# SCH_Modules.net
KiCad netlist of a schematic drawn in Altium Designer
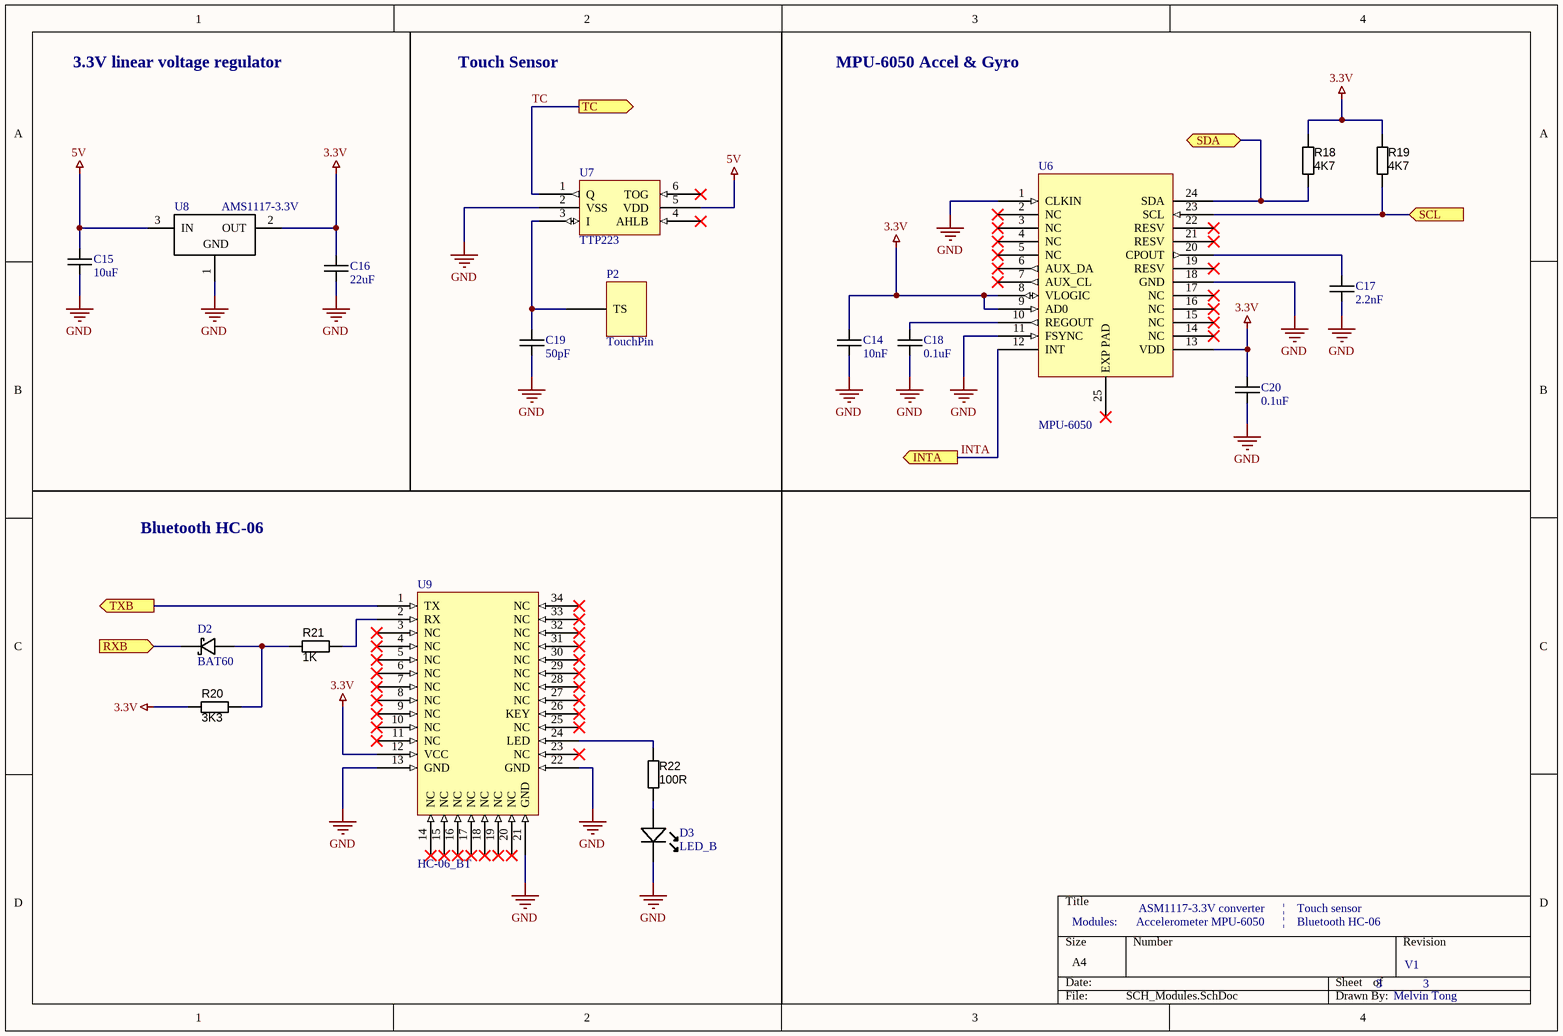
[diagram p0: SCH_Modules.SchDoc]

(export (version "E")
  (design (tool "Eeschema 10.0.6"))
  (components
    (comp (ref "C14")
      (value "10nF")
      (footprint "CAP_0805")
      (description "SMD 0805")
      (libsource (lib "Schlib_Sword") (part "CAP_10nF"))
    )
    (comp (ref "C15")
      (value "10uF")
      (footprint "CAP_1206")
      (description "SMD 0805/1206")
      (libsource (lib "Schlib_Sword") (part "CAP_10uF"))
    )
    (comp (ref "C16")
      (value "22uF")
      (footprint "CAP_1206")
      (description "SMD 1206")
      (libsource (lib "Schlib_Sword") (part "CAP_22uF"))
    )
    (comp (ref "C17")
      (value "2.2nF")
      (footprint "CAP_0805")
      (description "SMD 0805")
      (libsource (lib "Schlib_Sword") (part "CAP_2.2nF"))
    )
    (comp (ref "C18")
      (value "0.1uF")
      (footprint "CAP_0805")
      (description "SMD 0805")
      (libsource (lib "Schlib_Sword") (part "CAP_0.1uF"))
    )
    (comp (ref "C19")
      (value "50pF")
      (footprint "CAP_0805")
      (description "SMD 0805")
      (libsource (lib "Schlib_Sword") (part "CAP_50pF"))
    )
    (comp (ref "C20")
      (value "0.1uF")
      (footprint "CAP_0805")
      (description "SMD 0805")
      (libsource (lib "Schlib_Sword") (part "CAP_0.1uF"))
    )
    (comp (ref "D2")
      (value "BAT60")
      (footprint "SOD323")
      (description "Schottky Diode 3A, Vf~0.24V, Vr=10V")
      (libsource (lib "Schlib_Sword") (part "BAT60"))
    )
    (comp (ref "D3")
      (value "LED_B")
      (footprint "LED_0805")
      (description "SMD_0805 3V")
      (libsource (lib "Schlib_Sword") (part "LED_B"))
    )
    (comp (ref "P2")
      (value "TouchPin")
      (footprint "TouchPad")
      (libsource (lib "Schlib_Sword") (part "TouchPin"))
    )
    (comp (ref "R18")
      (value "4K7")
      (footprint "RESC3216X70N")
      (description "Resistor SMD, 1206")
      (libsource (lib "Schlib_Sword") (part "RES_4K7"))
    )
    (comp (ref "R19")
      (value "4K7")
      (footprint "RESC3216X70N")
      (description "Resistor SMD, 1206")
      (libsource (lib "Schlib_Sword") (part "RES_4K7"))
    )
    (comp (ref "R20")
      (value "3K3")
      (footprint "RESC3216X70N")
      (description "Resistor SMD, 1206")
      (libsource (lib "Schlib_Sword") (part "RES_3K3"))
    )
    (comp (ref "R21")
      (value "1K")
      (footprint "RESC3216X70N")
      (description "Resistor SMD, 1206")
      (libsource (lib "Schlib_Sword") (part "RES_1K"))
    )
    (comp (ref "R22")
      (value "100R")
      (footprint "RESC3216X70N")
      (description "Resistor SMD, 1206")
      (libsource (lib "Schlib_Sword") (part "RES_100R"))
    )
    (comp (ref "U6")
      (value "MPU-6050")
      (footprint "MPU-6050")
      (libsource (lib "Schlib_Sword") (part "MPU-6050"))
    )
    (comp (ref "U7")
      (value "TTP223")
      (footprint "TTP223-BA6")
      (libsource (lib "Schlib_Sword") (part "TTP223"))
    )
    (comp (ref "U8")
      (value "AMS1117-3.3V")
      (footprint "SOT223")
      (libsource (lib "Schlib_Sword") (part "AMS1117-3.3V"))
    )
    (comp (ref "U9")
      (value "HC-06_BT")
      (footprint "HC-06_BT")
      (libsource (lib "Schlib_Sword") (part "HC-06_BT"))
    )
  )
  (nets
    (net (code "1") (name "/INTA") (class "Default")
      (node (ref "U6") (pin "12") (pinfunction "INT_12") (pintype "open_collector"))
    )
    (net (code "2") (name "/RXB") (class "Default")
      (node (ref "D2") (pin "K") (pinfunction "K_K") (pintype "passive"))
    )
    (net (code "3") (name "/SCL") (class "Default")
      (node (ref "R19") (pin "2") (pinfunction "2_2") (pintype "passive"))
      (node (ref "U6") (pin "23") (pinfunction "SCL_23") (pintype "input"))
    )
    (net (code "4") (name "/SDA") (class "Default")
      (node (ref "R18") (pin "2") (pinfunction "2_2") (pintype "passive"))
      (node (ref "U6") (pin "24") (pinfunction "SDA_24") (pintype "open_collector"))
    )
    (net (code "5") (name "/TC") (class "Default")
      (node (ref "U7") (pin "1") (pinfunction "Q_1") (pintype "output"))
    )
    (net (code "6") (name "/TXB") (class "Default")
      (node (ref "U9") (pin "1") (pinfunction "TX_1") (pintype "input"))
    )
    (net (code "7") (name "3.3V") (class "Default")
      (node (ref "C14") (pin "2") (pintype "passive"))
      (node (ref "C16") (pin "1") (pintype "passive"))
      (node (ref "C20") (pin "2") (pintype "passive"))
      (node (ref "R18") (pin "1") (pinfunction "1_1") (pintype "passive"))
      (node (ref "R19") (pin "1") (pinfunction "1_1") (pintype "passive"))
      (node (ref "R20") (pin "1") (pinfunction "1_1") (pintype "passive"))
      (node (ref "U6") (pin "13") (pinfunction "VDD_13") (pintype "power_in"))
      (node (ref "U6") (pin "8") (pinfunction "VLOGIC_8") (pintype "bidirectional"))
      (node (ref "U6") (pin "9") (pinfunction "AD0_9") (pintype "input"))
      (node (ref "U8") (pin "2") (pinfunction "OUT_2") (pintype "power_in"))
      (node (ref "U9") (pin "12") (pinfunction "VCC_12") (pintype "input"))
    )
    (net (code "8") (name "5V") (class "Default")
      (node (ref "C15") (pin "1") (pintype "passive"))
      (node (ref "U7") (pin "5") (pinfunction "VDD_5") (pintype "power_in"))
      (node (ref "U8") (pin "3") (pinfunction "IN_3") (pintype "power_in"))
    )
    (net (code "9") (name "GND") (class "Default")
      (node (ref "C14") (pin "1") (pintype "passive"))
      (node (ref "C15") (pin "2") (pintype "passive"))
      (node (ref "C16") (pin "2") (pintype "passive"))
      (node (ref "C17") (pin "2") (pintype "passive"))
      (node (ref "C18") (pin "1") (pintype "passive"))
      (node (ref "C19") (pin "2") (pintype "passive"))
      (node (ref "C20") (pin "1") (pintype "passive"))
      (node (ref "D3") (pin "K") (pinfunction "K_K") (pintype "passive"))
      (node (ref "U6") (pin "1") (pinfunction "CLKIN_1") (pintype "input"))
      (node (ref "U6") (pin "11") (pinfunction "FSYNC_11") (pintype "input"))
      (node (ref "U6") (pin "18") (pinfunction "GND_18") (pintype "power_in"))
      (node (ref "U7") (pin "2") (pinfunction "VSS_2") (pintype "power_in"))
      (node (ref "U8") (pin "1") (pinfunction "ADJ_1") (pintype "power_in"))
      (node (ref "U9") (pin "13") (pinfunction "GND_13") (pintype "input"))
      (node (ref "U9") (pin "21") (pinfunction "GND_21") (pintype "input"))
      (node (ref "U9") (pin "22") (pinfunction "GND_22") (pintype "input"))
    )
    (net (code "10") (name "Net-(D2-PadA)") (class "Default")
      (node (ref "D2") (pin "A") (pinfunction "A_A") (pintype "passive"))
      (node (ref "R20") (pin "2") (pinfunction "2_2") (pintype "passive"))
      (node (ref "R21") (pin "1") (pinfunction "1_1") (pintype "passive"))
    )
    (net (code "11") (name "Net-(D3-PadA)") (class "Default")
      (node (ref "D3") (pin "A") (pinfunction "A_A") (pintype "passive"))
      (node (ref "R22") (pin "2") (pinfunction "2_2") (pintype "passive"))
    )
    (net (code "12") (name "Net-(P2-TS)") (class "Default")
      (node (ref "C19") (pin "1") (pintype "passive"))
      (node (ref "P2") (pin "1") (pinfunction "TS_1") (pintype "passive"))
      (node (ref "U7") (pin "3") (pinfunction "I_3") (pintype "bidirectional"))
    )
    (net (code "13") (name "Net-(U6-CPOUT)") (class "Default")
      (node (ref "C17") (pin "1") (pintype "passive"))
      (node (ref "U6") (pin "20") (pinfunction "CPOUT_20") (pintype "output"))
    )
    (net (code "14") (name "Net-(U6-REGOUT)") (class "Default")
      (node (ref "C18") (pin "2") (pintype "passive"))
      (node (ref "U6") (pin "10") (pinfunction "REGOUT_10") (pintype "output"))
    )
    (net (code "15") (name "Net-(U9-LED)") (class "Default")
      (node (ref "R22") (pin "1") (pinfunction "1_1") (pintype "passive"))
      (node (ref "U9") (pin "24") (pinfunction "LED_24") (pintype "input"))
    )
    (net (code "16") (name "Net-(U9-RX)") (class "Default")
      (node (ref "R21") (pin "2") (pinfunction "2_2") (pintype "passive"))
      (node (ref "U9") (pin "2") (pinfunction "RX_2") (pintype "input"))
    )
    (net (code "17") (name "unconnected-(U6-AUX_CL-Pad7)") (class "Default")
      (node (ref "U6") (pin "7") (pinfunction "AUX_CL_7") (pintype "output+no_connect"))
    )
    (net (code "18") (name "unconnected-(U6-AUX_DA-Pad6)") (class "Default")
      (node (ref "U6") (pin "6") (pinfunction "AUX_DA_6") (pintype "output+no_connect"))
    )
    (net (code "19") (name "unconnected-(U6-EXP_PAD-Pad25)") (class "Default")
      (node (ref "U6") (pin "25") (pinfunction "EXP_PAD_25") (pintype "passive+no_connect"))
    )
    (net (code "20") (name "unconnected-(U6-NC-Pad2)") (class "Default")
      (node (ref "U6") (pin "2") (pinfunction "NC_2") (pintype "passive+no_connect"))
    )
    (net (code "21") (name "unconnected-(U6-NC-Pad3)") (class "Default")
      (node (ref "U6") (pin "3") (pinfunction "NC_3") (pintype "passive+no_connect"))
    )
    (net (code "22") (name "unconnected-(U6-NC-Pad4)") (class "Default")
      (node (ref "U6") (pin "4") (pinfunction "NC_4") (pintype "passive+no_connect"))
    )
    (net (code "23") (name "unconnected-(U6-NC-Pad5)") (class "Default")
      (node (ref "U6") (pin "5") (pinfunction "NC_5") (pintype "passive+no_connect"))
    )
    (net (code "24") (name "unconnected-(U6-NC-Pad14)") (class "Default")
      (node (ref "U6") (pin "14") (pinfunction "NC_14") (pintype "passive+no_connect"))
    )
    (net (code "25") (name "unconnected-(U6-NC-Pad15)") (class "Default")
      (node (ref "U6") (pin "15") (pinfunction "NC_15") (pintype "passive+no_connect"))
    )
    (net (code "26") (name "unconnected-(U6-NC-Pad16)") (class "Default")
      (node (ref "U6") (pin "16") (pinfunction "NC_16") (pintype "passive+no_connect"))
    )
    (net (code "27") (name "unconnected-(U6-NC-Pad17)") (class "Default")
      (node (ref "U6") (pin "17") (pinfunction "NC_17") (pintype "passive+no_connect"))
    )
    (net (code "28") (name "unconnected-(U6-RESV-Pad19)") (class "Default")
      (node (ref "U6") (pin "19") (pinfunction "RESV_19") (pintype "passive+no_connect"))
    )
    (net (code "29") (name "unconnected-(U6-RESV-Pad21)") (class "Default")
      (node (ref "U6") (pin "21") (pinfunction "RESV_21") (pintype "passive+no_connect"))
    )
    (net (code "30") (name "unconnected-(U6-RESV-Pad22)") (class "Default")
      (node (ref "U6") (pin "22") (pinfunction "RESV_22") (pintype "passive+no_connect"))
    )
    (net (code "31") (name "unconnected-(U7-AHLB-Pad4)") (class "Default")
      (node (ref "U7") (pin "4") (pinfunction "AHLB_4") (pintype "input+no_connect"))
    )
    (net (code "32") (name "unconnected-(U7-TOG-Pad6)") (class "Default")
      (node (ref "U7") (pin "6") (pinfunction "TOG_6") (pintype "input+no_connect"))
    )
    (net (code "33") (name "unconnected-(U9-KEY-Pad26)") (class "Default")
      (node (ref "U9") (pin "26") (pinfunction "KEY_26") (pintype "input+no_connect"))
    )
    (net (code "34") (name "unconnected-(U9-NC-Pad3)") (class "Default")
      (node (ref "U9") (pin "3") (pinfunction "NC_3") (pintype "input+no_connect"))
    )
    (net (code "35") (name "unconnected-(U9-NC-Pad4)") (class "Default")
      (node (ref "U9") (pin "4") (pinfunction "NC_4") (pintype "input+no_connect"))
    )
    (net (code "36") (name "unconnected-(U9-NC-Pad5)") (class "Default")
      (node (ref "U9") (pin "5") (pinfunction "NC_5") (pintype "input+no_connect"))
    )
    (net (code "37") (name "unconnected-(U9-NC-Pad6)") (class "Default")
      (node (ref "U9") (pin "6") (pinfunction "NC_6") (pintype "input+no_connect"))
    )
    (net (code "38") (name "unconnected-(U9-NC-Pad7)") (class "Default")
      (node (ref "U9") (pin "7") (pinfunction "NC_7") (pintype "input+no_connect"))
    )
    (net (code "39") (name "unconnected-(U9-NC-Pad8)") (class "Default")
      (node (ref "U9") (pin "8") (pinfunction "NC_8") (pintype "input+no_connect"))
    )
    (net (code "40") (name "unconnected-(U9-NC-Pad9)") (class "Default")
      (node (ref "U9") (pin "9") (pinfunction "NC_9") (pintype "input+no_connect"))
    )
    (net (code "41") (name "unconnected-(U9-NC-Pad10)") (class "Default")
      (node (ref "U9") (pin "10") (pinfunction "NC_10") (pintype "input+no_connect"))
    )
    (net (code "42") (name "unconnected-(U9-NC-Pad11)") (class "Default")
      (node (ref "U9") (pin "11") (pinfunction "NC_11") (pintype "input+no_connect"))
    )
    (net (code "43") (name "unconnected-(U9-NC-Pad14)") (class "Default")
      (node (ref "U9") (pin "14") (pinfunction "NC_14") (pintype "input+no_connect"))
    )
    (net (code "44") (name "unconnected-(U9-NC-Pad15)") (class "Default")
      (node (ref "U9") (pin "15") (pinfunction "NC_15") (pintype "input+no_connect"))
    )
    (net (code "45") (name "unconnected-(U9-NC-Pad16)") (class "Default")
      (node (ref "U9") (pin "16") (pinfunction "NC_16") (pintype "input+no_connect"))
    )
    (net (code "46") (name "unconnected-(U9-NC-Pad17)") (class "Default")
      (node (ref "U9") (pin "17") (pinfunction "NC_17") (pintype "input+no_connect"))
    )
    (net (code "47") (name "unconnected-(U9-NC-Pad18)") (class "Default")
      (node (ref "U9") (pin "18") (pinfunction "NC_18") (pintype "input+no_connect"))
    )
    (net (code "48") (name "unconnected-(U9-NC-Pad19)") (class "Default")
      (node (ref "U9") (pin "19") (pinfunction "NC_19") (pintype "input+no_connect"))
    )
    (net (code "49") (name "unconnected-(U9-NC-Pad20)") (class "Default")
      (node (ref "U9") (pin "20") (pinfunction "NC_20") (pintype "input+no_connect"))
    )
    (net (code "50") (name "unconnected-(U9-NC-Pad23)") (class "Default")
      (node (ref "U9") (pin "23") (pinfunction "NC_23") (pintype "input+no_connect"))
    )
    (net (code "51") (name "unconnected-(U9-NC-Pad25)") (class "Default")
      (node (ref "U9") (pin "25") (pinfunction "NC_25") (pintype "input+no_connect"))
    )
    (net (code "52") (name "unconnected-(U9-NC-Pad27)") (class "Default")
      (node (ref "U9") (pin "27") (pinfunction "NC_27") (pintype "input+no_connect"))
    )
    (net (code "53") (name "unconnected-(U9-NC-Pad28)") (class "Default")
      (node (ref "U9") (pin "28") (pinfunction "NC_28") (pintype "input+no_connect"))
    )
    (net (code "54") (name "unconnected-(U9-NC-Pad29)") (class "Default")
      (node (ref "U9") (pin "29") (pinfunction "NC_29") (pintype "input+no_connect"))
    )
    (net (code "55") (name "unconnected-(U9-NC-Pad30)") (class "Default")
      (node (ref "U9") (pin "30") (pinfunction "NC_30") (pintype "input+no_connect"))
    )
    (net (code "56") (name "unconnected-(U9-NC-Pad31)") (class "Default")
      (node (ref "U9") (pin "31") (pinfunction "NC_31") (pintype "input+no_connect"))
    )
    (net (code "57") (name "unconnected-(U9-NC-Pad32)") (class "Default")
      (node (ref "U9") (pin "32") (pinfunction "NC_32") (pintype "input+no_connect"))
    )
    (net (code "58") (name "unconnected-(U9-NC-Pad33)") (class "Default")
      (node (ref "U9") (pin "33") (pinfunction "NC_33") (pintype "input+no_connect"))
    )
    (net (code "59") (name "unconnected-(U9-NC-Pad34)") (class "Default")
      (node (ref "U9") (pin "34") (pinfunction "NC_34") (pintype "input+no_connect"))
    )
  )
)
